# singlefilter.net
KiCad netlist of a schematic drawn in Altium Designer
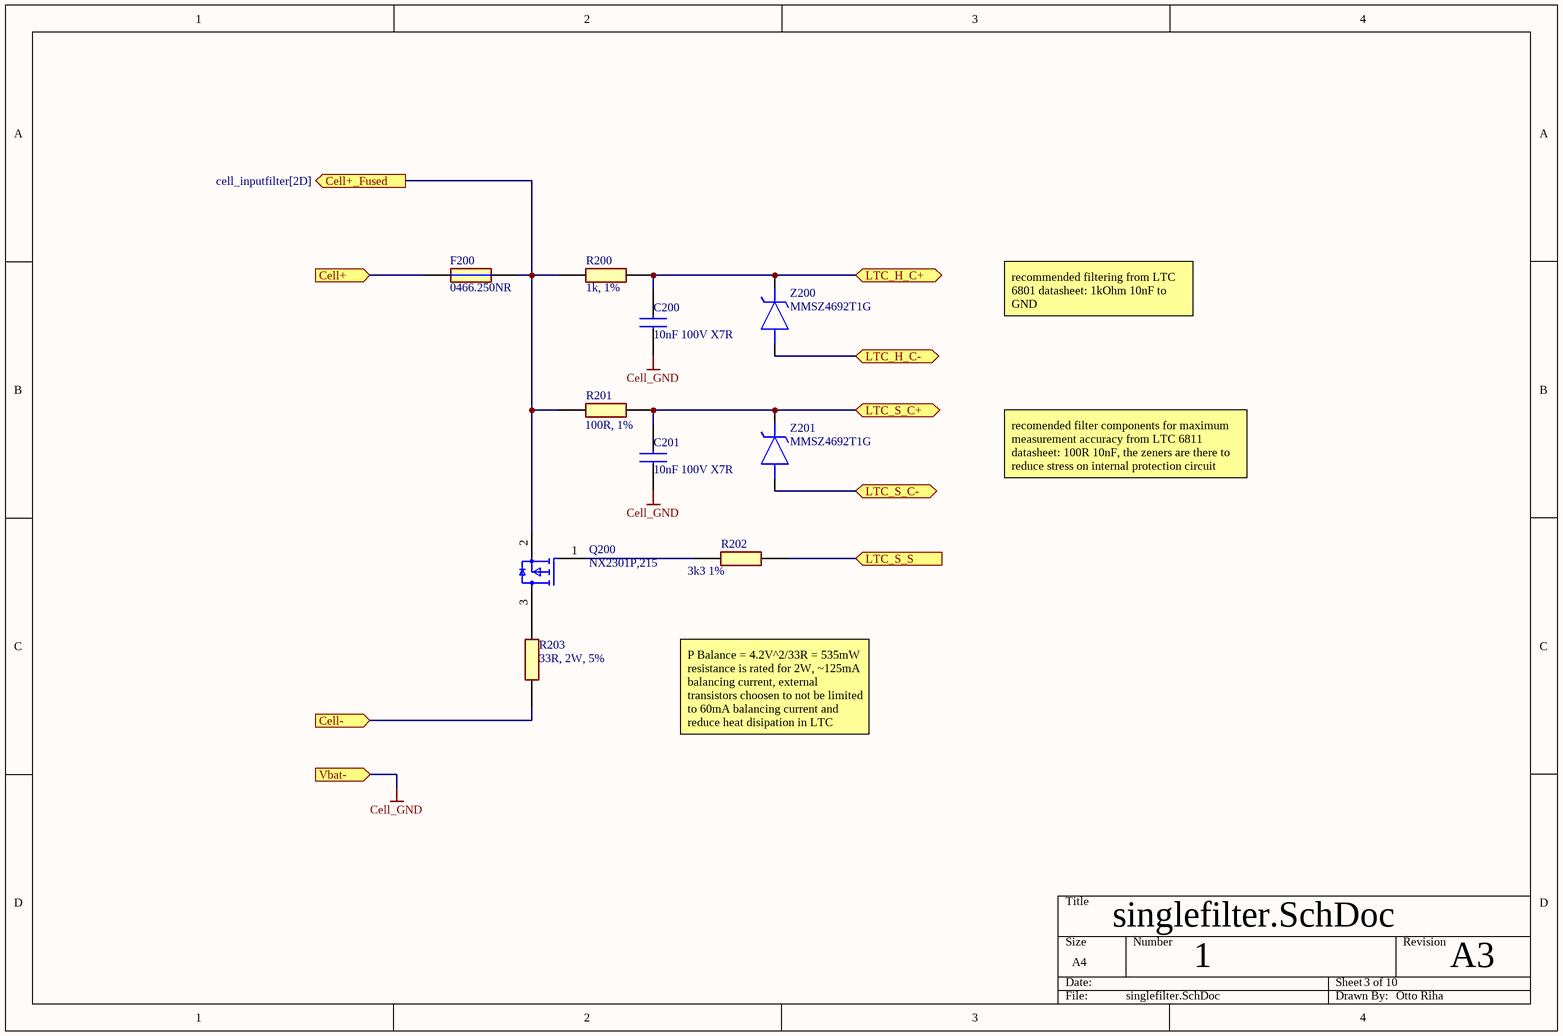
[diagram p0: singlefilter.SchDoc]

(export (version "E")
  (design (tool "Eeschema 10.0.6"))
  (components
    (comp (ref "C200")
      (value "10nF 100V X7R")
      (footprint "SamacSys:CAPC1608X90N")
      (description "Capacitor 10nF 100V X7R")
      (fields
        (field (name "MANUFACTURER_PART_NUMBER") "06031C103K4Z2A")
        (field (name "MOUSER PART NUMBER") "581-06031C103K4Z2A")
      )
      (libsource (lib "SamacSys") (part "06031C103K4Z2A"))
    )
    (comp (ref "C201")
      (value "10nF 100V X7R")
      (footprint "SamacSys:CAPC1608X90N")
      (description "Capacitor 10nF 100V X7R")
      (fields
        (field (name "MANUFACTURER_PART_NUMBER") "06031C103K4Z2A")
        (field (name "MOUSER PART NUMBER") "581-06031C103K4Z2A")
      )
      (libsource (lib "SamacSys") (part "06031C103K4Z2A"))
    )
    (comp (ref "F200")
      (value "0466.250NR")
      (footprint "SamacSys:FUSC3215X66N")
      (description "Fuse")
      (fields (field (name "MOUSER PART NUMBER") "576-0466.250NR"))
      (libsource (lib "SamacSys") (part "0466.250NR"))
    )
    (comp (ref "Q200")
      (value "NX2301P,215")
      (footprint "SamacSys:SOT95P230X110-3N")
      (description "Integrated Circuit")
      (fields (field (name "MOUSER PART NUMBER") "771-NX2301P215"))
      (libsource (lib "SamacSys") (part "NX2301P,215"))
    )
    (comp (ref "R200")
      (value "1k, 1%")
      (footprint "SamacSys:RESC1608X55N")
      (description "Resistor 1k, 1%")
      (fields
        (field (name "MANUFACTURER_PART_NUMBER") "AF0603FR-071KL")
        (field (name "MOUSER PART NUMBER") "603-AF0603FR-071KL")
      )
      (libsource (lib "SamacSys") (part "AF0603FR-071KL"))
    )
    (comp (ref "R201")
      (value "100R, 1%")
      (footprint "SamacSys:RESC1608X50N")
      (description "Resistor 100R, 1%")
      (fields
        (field (name "MANUFACTURER_PART_NUMBER") "CRCW0603100RFKEA")
        (field (name "MOUSER PART NUMBER") "71-CRCW0603-100-E3")
      )
      (libsource (lib "SamacSys") (part "CRCW0603100RFKEA"))
    )
    (comp (ref "R202")
      (value "3k3 1%")
      (footprint "SamacSys:RESC1608X55N")
      (description "Resistor 3k3 1%")
      (fields
        (field (name "MANUFACTURER_PART_NUMBER") "CRGH0603F3K3")
        (field (name "MOUSER PART NUMBER") "279-CRGH0603F3K3")
      )
      (libsource (lib "SamacSys") (part "CRGH0603F3K3"))
    )
    (comp (ref "R203")
      (value "33R, 2W, 5%")
      (footprint "SamacSys:RESC6331X80N")
      (description "Resistor 33R, 2W, 5%")
      (fields
        (field (name "MANUFACTURER_PART_NUMBER") "CRM2512-JW-330ELF")
        (field (name "MOUSER PART NUMBER") "652-CRM2512JW330ELF")
      )
      (libsource (lib "SamacSys") (part "CRM2512-JW-330ELF"))
    )
    (comp (ref "Z200")
      (value "MMSZ4692T1G")
      (footprint "SamacSys:SOD3716X135N")
      (description "Zener Diode 6.8V")
      (fields (field (name "MOUSER PART NUMBER") "863-MMSZ4692T1G"))
      (libsource (lib "SamacSys") (part "MMSZ4692T1G"))
    )
    (comp (ref "Z201")
      (value "MMSZ4692T1G")
      (footprint "SamacSys:SOD3716X135N")
      (description "Zener Diode 6.8V")
      (fields (field (name "MOUSER PART NUMBER") "863-MMSZ4692T1G"))
      (libsource (lib "SamacSys") (part "MMSZ4692T1G"))
    )
  )
  (nets
    (net (code "1") (name "/Cell+") (class "Default")
      (node (ref "F200") (pin "1") (pinfunction "1_1") (pintype "passive"))
    )
    (net (code "2") (name "/Cell+_Fused") (class "Default")
      (node (ref "F200") (pin "2") (pinfunction "2_2") (pintype "passive"))
      (node (ref "Q200") (pin "2") (pinfunction "S_2") (pintype "passive"))
      (node (ref "R200") (pin "1") (pinfunction "1_1") (pintype "passive"))
      (node (ref "R201") (pin "1") (pinfunction "1_1") (pintype "passive"))
    )
    (net (code "3") (name "/Cell-") (class "Default")
      (node (ref "R203") (pin "1") (pinfunction "1_1") (pintype "passive"))
    )
    (net (code "4") (name "/LTC_H_C+") (class "Default")
      (node (ref "C200") (pin "2") (pinfunction "2_2") (pintype "passive"))
      (node (ref "R200") (pin "2") (pinfunction "2_2") (pintype "passive"))
      (node (ref "Z200") (pin "1") (pinfunction "K_1") (pintype "passive"))
    )
    (net (code "5") (name "/LTC_H_C-") (class "Default")
      (node (ref "Z200") (pin "2") (pinfunction "A_2") (pintype "passive"))
    )
    (net (code "6") (name "/LTC_S_C+") (class "Default")
      (node (ref "C201") (pin "2") (pinfunction "2_2") (pintype "passive"))
      (node (ref "R201") (pin "2") (pinfunction "2_2") (pintype "passive"))
      (node (ref "Z201") (pin "1") (pinfunction "K_1") (pintype "passive"))
    )
    (net (code "7") (name "/LTC_S_C-") (class "Default")
      (node (ref "Z201") (pin "2") (pinfunction "A_2") (pintype "passive"))
    )
    (net (code "8") (name "/LTC_S_S") (class "Default")
      (node (ref "R202") (pin "2") (pinfunction "2_2") (pintype "passive"))
    )
    (net (code "9") (name "Cell_GND") (class "Default")
      (node (ref "C200") (pin "1") (pinfunction "1_1") (pintype "passive"))
      (node (ref "C201") (pin "1") (pinfunction "1_1") (pintype "passive"))
    )
    (net (code "10") (name "Net-(Q200-D)") (class "Default")
      (node (ref "Q200") (pin "3") (pinfunction "D_3") (pintype "passive"))
      (node (ref "R203") (pin "2") (pinfunction "2_2") (pintype "passive"))
    )
    (net (code "11") (name "Net-(Q200-G)") (class "Default")
      (node (ref "Q200") (pin "1") (pinfunction "G_1") (pintype "passive"))
      (node (ref "R202") (pin "1") (pinfunction "1_1") (pintype "passive"))
    )
  )
)
